# XLR-M_Breakout.net
KiCad netlist of a schematic drawn in EAGLE
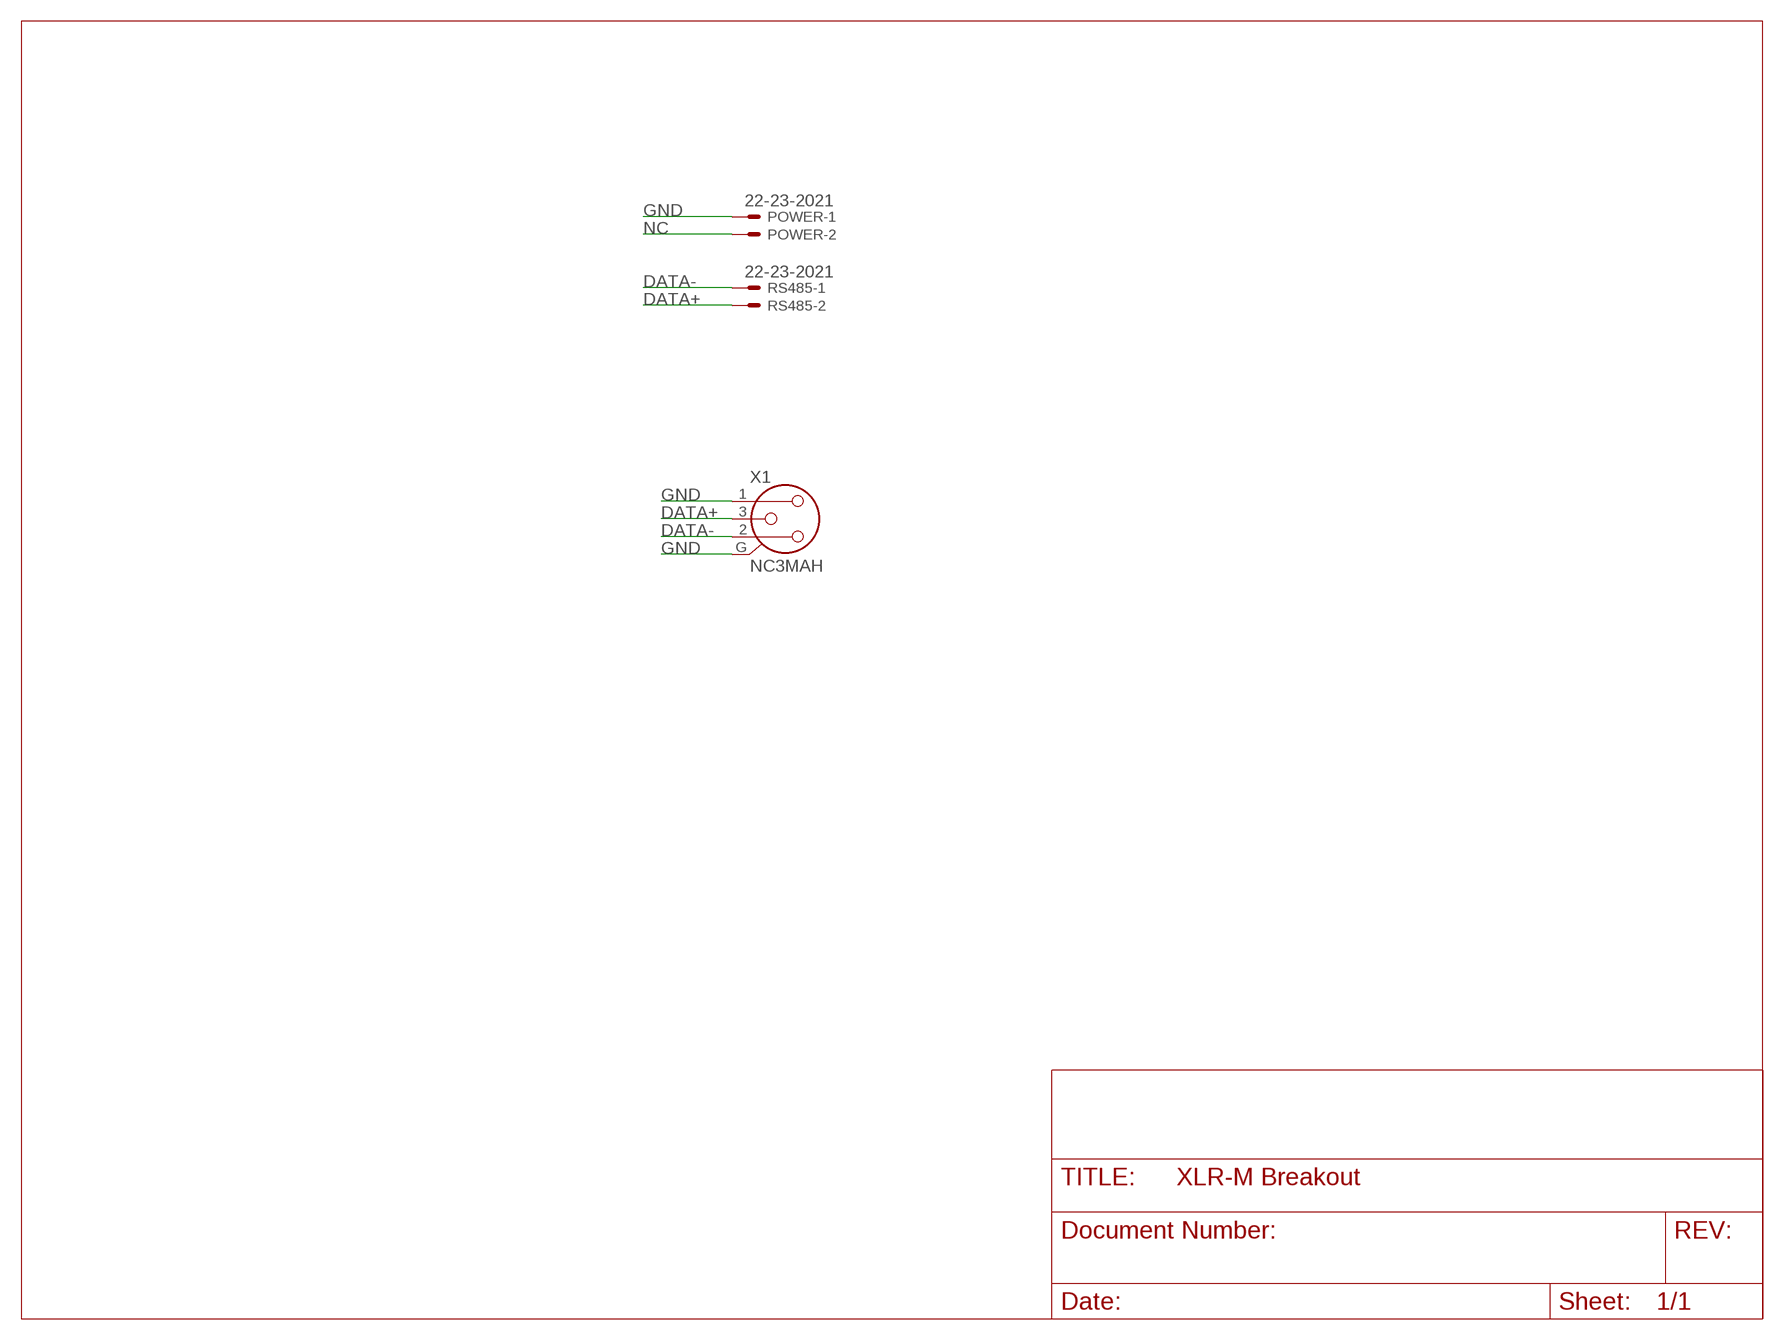
[diagram p0: schematic, sheet 1]

(export (version "E")
  (design (tool "Eeschema 10.0.6"))
  (components
    (comp (ref "POWER")
      (value "22-23-2021")
      (footprint "eagle-import:22-23-2021")
      (fields (field (name "MF") "MOLEX"))
      (libsource (lib "eagle-import") (part "22-23-2021"))
    )
    (comp (ref "RS485")
      (value "22-23-2021")
      (footprint "eagle-import:22-23-2021")
      (fields (field (name "MF") "MOLEX"))
      (libsource (lib "eagle-import") (part "22-23-2021"))
    )
    (comp (ref "X1")
      (value "NC3MAH")
      (footprint "eagle-import:NC3MBH")
      (fields (field (name "MF") "NEUTRIK") (field (name "MPN") "NC3MBH"))
      (libsource (lib "eagle-import") (part "NC3MBH"))
    )
  )
  (nets
    (net (code "1") (name "/DATA+") (class "Default")
      (node (ref "RS485") (pin "2") (pinfunction "S_2") (pintype "passive"))
      (node (ref "X1") (pin "3") (pinfunction "3_3") (pintype "passive"))
    )
    (net (code "2") (name "/DATA-") (class "Default")
      (node (ref "RS485") (pin "1") (pinfunction "S_1") (pintype "passive"))
      (node (ref "X1") (pin "2") (pinfunction "2_2") (pintype "passive"))
    )
    (net (code "3") (name "/GND") (class "Default")
      (node (ref "POWER") (pin "1") (pinfunction "S_1") (pintype "passive"))
      (node (ref "X1") (pin "1") (pinfunction "1_1") (pintype "passive"))
      (node (ref "X1") (pin "G") (pinfunction "G_G") (pintype "passive"))
    )
    (net (code "4") (name "/NC") (class "Default")
      (node (ref "POWER") (pin "2") (pinfunction "S_2") (pintype "passive"))
    )
  )
)
